# Geral.net
KiCad netlist of a schematic drawn in Altium Designer
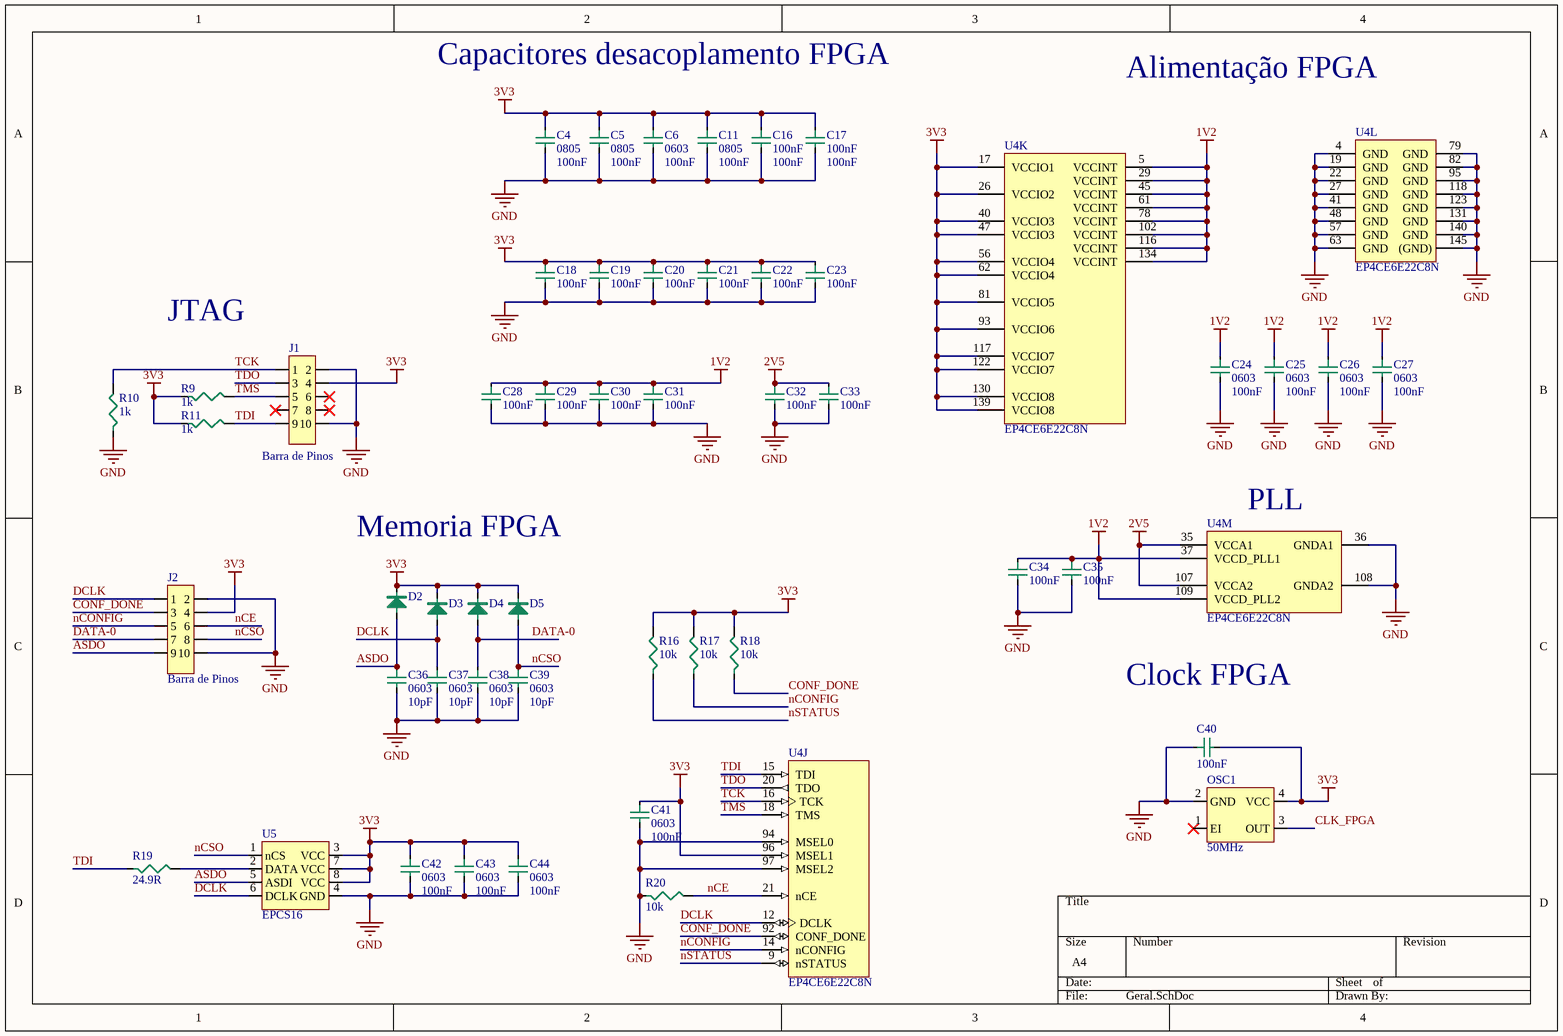
[diagram p0: Geral.SchDoc]

(export (version "E")
  (design (tool "Eeschema 10.0.6"))
  (components
    (comp (ref "C4")
      (value "0805")
      (footprint "0603C")
      (description "Capacitor SMD 0603")
      (fields (field (name "ALTIUM_VALUE") "100nF"))
      (libsource (lib "") (part "Capacitor SMD 0603_1"))
    )
    (comp (ref "C5")
      (value "0805")
      (footprint "0603C")
      (description "Capacitor SMD 0603")
      (fields (field (name "ALTIUM_VALUE") "100nF"))
      (libsource (lib "") (part "Capacitor SMD 0603_1"))
    )
    (comp (ref "C6")
      (value "0603")
      (footprint "0603C")
      (description "Capacitor SMD 0603")
      (fields (field (name "ALTIUM_VALUE") "100nF"))
      (libsource (lib "") (part "Capacitor SMD 0603_1"))
    )
    (comp (ref "C11")
      (value "0805")
      (footprint "0603C")
      (description "Capacitor SMD 0603")
      (fields (field (name "ALTIUM_VALUE") "100nF"))
      (libsource (lib "") (part "Capacitor SMD 0603_1"))
    )
    (comp (ref "C16")
      (value "100nF")
      (footprint "0603C")
      (description "Capacitor SMD 0603")
      (fields (field (name "ALTIUM_VALUE") "100nF"))
      (libsource (lib "RLC_Integrated_Library") (part "Capacitor SMD 0603"))
    )
    (comp (ref "C17")
      (value "100nF")
      (footprint "0603C")
      (description "Capacitor SMD 0603")
      (fields (field (name "ALTIUM_VALUE") "100nF"))
      (libsource (lib "RLC_Integrated_Library") (part "Capacitor SMD 0603"))
    )
    (comp (ref "C18")
      (value "100nF")
      (footprint "0603C")
      (description "Capacitor SMD 0603")
      (libsource (lib "RLC_Integrated_Library") (part "Capacitor SMD 0603"))
    )
    (comp (ref "C19")
      (value "100nF")
      (footprint "0603C")
      (description "Capacitor SMD 0603")
      (libsource (lib "RLC_Integrated_Library") (part "Capacitor SMD 0603"))
    )
    (comp (ref "C20")
      (value "100nF")
      (footprint "0603C")
      (description "Capacitor SMD 0603")
      (libsource (lib "RLC_Integrated_Library") (part "Capacitor SMD 0603"))
    )
    (comp (ref "C21")
      (value "100nF")
      (footprint "0603C")
      (description "Capacitor SMD 0603")
      (libsource (lib "RLC_Integrated_Library") (part "Capacitor SMD 0603"))
    )
    (comp (ref "C22")
      (value "100nF")
      (footprint "0603C")
      (description "Capacitor SMD 0603")
      (libsource (lib "RLC_Integrated_Library") (part "Capacitor SMD 0603"))
    )
    (comp (ref "C23")
      (value "100nF")
      (footprint "0603C")
      (description "Capacitor SMD 0603")
      (libsource (lib "RLC_Integrated_Library") (part "Capacitor SMD 0603"))
    )
    (comp (ref "C24")
      (value "0603")
      (footprint "0603C")
      (description "Capacitor SMD 0603")
      (fields (field (name "ALTIUM_VALUE") "100nF"))
      (libsource (lib "") (part "Capacitor SMD 0603_1"))
    )
    (comp (ref "C25")
      (value "0603")
      (footprint "0603C")
      (description "Capacitor SMD 0603")
      (fields (field (name "ALTIUM_VALUE") "100nF"))
      (libsource (lib "") (part "Capacitor SMD 0603_1"))
    )
    (comp (ref "C26")
      (value "0603")
      (footprint "0603C")
      (description "Capacitor SMD 0603")
      (fields (field (name "ALTIUM_VALUE") "100nF"))
      (libsource (lib "") (part "Capacitor SMD 0603_1"))
    )
    (comp (ref "C27")
      (value "0603")
      (footprint "0603C")
      (description "Capacitor SMD 0603")
      (fields (field (name "ALTIUM_VALUE") "100nF"))
      (libsource (lib "") (part "Capacitor SMD 0603_1"))
    )
    (comp (ref "C28")
      (value "100nF")
      (footprint "0603C")
      (description "Capacitor SMD 0603")
      (libsource (lib "RLC_Integrated_Library") (part "Capacitor SMD 0603"))
    )
    (comp (ref "C29")
      (value "100nF")
      (footprint "0603C")
      (description "Capacitor SMD 0603")
      (libsource (lib "RLC_Integrated_Library") (part "Capacitor SMD 0603"))
    )
    (comp (ref "C30")
      (value "100nF")
      (footprint "0603C")
      (description "Capacitor SMD 0603")
      (libsource (lib "RLC_Integrated_Library") (part "Capacitor SMD 0603"))
    )
    (comp (ref "C31")
      (value "100nF")
      (footprint "0603C")
      (description "Capacitor SMD 0603")
      (libsource (lib "RLC_Integrated_Library") (part "Capacitor SMD 0603"))
    )
    (comp (ref "C32")
      (value "100nF")
      (footprint "0603C")
      (description "Capacitor SMD 0603")
      (libsource (lib "RLC_Integrated_Library") (part "Capacitor SMD 0603"))
    )
    (comp (ref "C33")
      (value "100nF")
      (footprint "0603C")
      (description "Capacitor SMD 0603")
      (libsource (lib "RLC_Integrated_Library") (part "Capacitor SMD 0603"))
    )
    (comp (ref "C34")
      (value "100nF")
      (footprint "0603C")
      (description "Capacitor SMD 0603")
      (libsource (lib "RLC_Integrated_Library") (part "Capacitor SMD 0603"))
    )
    (comp (ref "C35")
      (value "100nF")
      (footprint "0603C")
      (description "Capacitor SMD 0603")
      (libsource (lib "RLC_Integrated_Library") (part "Capacitor SMD 0603"))
    )
    (comp (ref "C36")
      (value "0603")
      (footprint "0603C")
      (description "Capacitor SMD 0603")
      (fields (field (name "ALTIUM_VALUE") "10pF"))
      (libsource (lib "") (part "Capacitor SMD 0603_1"))
    )
    (comp (ref "C37")
      (value "0603")
      (footprint "0603C")
      (description "Capacitor SMD 0603")
      (fields (field (name "ALTIUM_VALUE") "10pF"))
      (libsource (lib "") (part "Capacitor SMD 0603_1"))
    )
    (comp (ref "C38")
      (value "0603")
      (footprint "0603C")
      (description "Capacitor SMD 0603")
      (fields (field (name "ALTIUM_VALUE") "10pF"))
      (libsource (lib "") (part "Capacitor SMD 0603_1"))
    )
    (comp (ref "C39")
      (value "0603")
      (footprint "0603C")
      (description "Capacitor SMD 0603")
      (fields (field (name "ALTIUM_VALUE") "10pF"))
      (libsource (lib "") (part "Capacitor SMD 0603_1"))
    )
    (comp (ref "C40")
      (value "100nF")
      (footprint "0603C")
      (description "Capacitor SMD 0603")
      (fields (field (name "Comment") "10pF"))
      (libsource (lib "") (part "Capacitor SMD 0603_1"))
    )
    (comp (ref "C41")
      (value "0603")
      (footprint "0603C")
      (description "Capacitor SMD 0603")
      (fields (field (name "ALTIUM_VALUE") "100nF"))
      (libsource (lib "") (part "Capacitor SMD 0603_1"))
    )
    (comp (ref "C42")
      (value "0603")
      (footprint "0603C")
      (description "Capacitor SMD 0603")
      (fields (field (name "ALTIUM_VALUE") "100nF"))
      (libsource (lib "") (part "Capacitor SMD 0603_1"))
    )
    (comp (ref "C43")
      (value "0603")
      (footprint "0603C")
      (description "Capacitor SMD 0603")
      (fields (field (name "ALTIUM_VALUE") "100nF"))
      (libsource (lib "") (part "Capacitor SMD 0603_1"))
    )
    (comp (ref "C44")
      (value "0603")
      (footprint "0603C")
      (description "Capacitor SMD 0603")
      (fields (field (name "ALTIUM_VALUE") "100nF"))
      (libsource (lib "") (part "Capacitor SMD 0603_1"))
    )
    (comp (ref "D2")
      (value "1N4148 SMD")
      (footprint "DIODE SMD LL-34")
      (description "Diodo Sinal SMD LL-34")
      (libsource (lib "Diodo_Transistor_Integrated_Library") (part "Diodo Sinal SMD 1N4148"))
    )
    (comp (ref "D3")
      (value "1N4148 SMD")
      (footprint "DIODE SMD LL-34")
      (description "Diodo Sinal SMD LL-34")
      (libsource (lib "Diodo_Transistor_Integrated_Library") (part "Diodo Sinal SMD 1N4148"))
    )
    (comp (ref "D4")
      (value "1N4148 SMD")
      (footprint "DIODE SMD LL-34")
      (description "Diodo Sinal SMD LL-34")
      (libsource (lib "Diodo_Transistor_Integrated_Library") (part "Diodo Sinal SMD 1N4148"))
    )
    (comp (ref "D5")
      (value "1N4148 SMD")
      (footprint "DIODE SMD LL-34")
      (description "Diodo Sinal SMD LL-34")
      (libsource (lib "Diodo_Transistor_Integrated_Library") (part "Diodo Sinal SMD 1N4148"))
    )
    (comp (ref "J1")
      (value "Barra de Pinos")
      (footprint "BPDC-10")
      (description "Barra 5X2 Pinos PTH")
      (fields (field (name "MANUFACTURER") "Metaltex"))
      (libsource (lib "Schlib1") (part "Barra 5X2 Pinos PTH"))
    )
    (comp (ref "J2")
      (value "Barra de Pinos")
      (footprint "BPDC-10")
      (description "Barra 5X2 Pinos PTH")
      (fields (field (name "MANUFACTURER") "Metaltex"))
      (libsource (lib "Schlib1") (part "Barra 5X2 Pinos PTH"))
    )
    (comp (ref "OSC1")
      (value "50MHz")
      (footprint "OSC CB3LV")
      (description "OSC XO 50.00MHZ HCMOS TTL SMD")
      (libsource (lib "Schlib1") (part "OSCILLATOR_INEP"))
    )
    (comp (ref "R9")
      (value "1k")
      (footprint "0603")
      (description "Resistor SMD 0603 1/10 W")
      (fields (field (name "Comment") "0603"))
      (libsource (lib "RLC_Integrated_Library") (part "Resistor SMD 0603 1/10 W"))
    )
    (comp (ref "R10")
      (value "1k")
      (footprint "0603")
      (description "Resistor SMD 0603 1/10 W")
      (fields (field (name "Comment") "0603"))
      (libsource (lib "RLC_Integrated_Library") (part "Resistor SMD 0603 1/10 W"))
    )
    (comp (ref "R11")
      (value "1k")
      (footprint "0603")
      (description "Resistor SMD 0603 1/10 W")
      (fields (field (name "Comment") "0603"))
      (libsource (lib "RLC_Integrated_Library") (part "Resistor SMD 0603 1/10 W"))
    )
    (comp (ref "R16")
      (value "10k")
      (footprint "0603")
      (description "Resistor SMD 0603 1/10 W")
      (fields (field (name "Comment") "100R"))
      (libsource (lib "RLC_Integrated_Library") (part "Resistor SMD 0603 1/10 W"))
    )
    (comp (ref "R17")
      (value "10k")
      (footprint "0603")
      (description "Resistor SMD 0603 1/10 W")
      (fields (field (name "Comment") "1K"))
      (libsource (lib "RLC_Integrated_Library") (part "Resistor SMD 0603 1/10 W"))
    )
    (comp (ref "R18")
      (value "10k")
      (footprint "0603")
      (description "Resistor SMD 0603 1/10 W")
      (fields (field (name "Comment") "1K"))
      (libsource (lib "RLC_Integrated_Library") (part "Resistor SMD 0603 1/10 W"))
    )
    (comp (ref "R19")
      (value "24.9R")
      (footprint "0603")
      (description "Resistor SMD 0603 1/10 W")
      (fields (field (name "Comment") "1K"))
      (libsource (lib "RLC_Integrated_Library") (part "Resistor SMD 0603 1/10 W"))
    )
    (comp (ref "R20")
      (value "10k")
      (footprint "0603")
      (description "Resistor SMD 0603 1/10 W")
      (fields (field (name "Comment") "10K"))
      (libsource (lib "RLC_Integrated_Library") (part "Resistor SMD 0603 1/10 W"))
    )
    (comp (ref "U4")
      (value "EP4CE6E22C8N")
      (footprint "EQFP144_M")
      (description "IC FPGA 91 I/O 144EQFP")
      (libsource (lib "Schlib1") (part "EP4CE6E22C8N"))
    )
    (comp (ref "U5")
      (value "EPCS16")
      (footprint "SOIC8")
      (description "IC CONFIG DEVICE 16MBIT 8SOIC")
      (libsource (lib "Schlib1") (part "EPCS16SI8N"))
    )
  )
  (nets
    (net (code "1") (name "/ASDO") (class "Default")
      (node (ref "C36") (pin "1") (pinfunction "1_1") (pintype "passive"))
      (node (ref "D2") (pin "A") (pinfunction "A_A") (pintype "passive"))
      (node (ref "J2") (pin "9") (pinfunction "9_9") (pintype "passive"))
      (node (ref "U5") (pin "5") (pinfunction "ASDI_5") (pintype "passive"))
    )
    (net (code "2") (name "/CLK_FPGA") (class "Default")
      (node (ref "OSC1") (pin "3") (pinfunction "OUT_3") (pintype "passive"))
    )
    (net (code "3") (name "/CONF_DONE") (class "Default")
      (node (ref "J2") (pin "3") (pinfunction "3_3") (pintype "passive"))
      (node (ref "R18") (pin "1") (pinfunction "1_1") (pintype "passive"))
      (node (ref "U4") (pin "92") (pinfunction "CONF_DONE_92") (pintype "bidirectional"))
    )
    (net (code "4") (name "/DATA-0") (class "Default")
      (node (ref "C38") (pin "1") (pinfunction "1_1") (pintype "passive"))
      (node (ref "D4") (pin "A") (pinfunction "A_A") (pintype "passive"))
      (node (ref "J2") (pin "7") (pinfunction "7_7") (pintype "passive"))
    )
    (net (code "5") (name "/DCLK") (class "Default")
      (node (ref "C37") (pin "1") (pinfunction "1_1") (pintype "passive"))
      (node (ref "D3") (pin "A") (pinfunction "A_A") (pintype "passive"))
      (node (ref "J2") (pin "1") (pinfunction "1_1") (pintype "passive"))
      (node (ref "U4") (pin "12") (pinfunction "DCLK_12") (pintype "bidirectional"))
      (node (ref "U5") (pin "6") (pinfunction "DCLK_6") (pintype "passive"))
    )
    (net (code "6") (name "/TCK") (class "Default")
      (node (ref "J1") (pin "1") (pinfunction "1_1") (pintype "passive"))
      (node (ref "R10") (pin "2") (pinfunction "2_2") (pintype "passive"))
      (node (ref "U4") (pin "16") (pinfunction "TCK_16") (pintype "input"))
    )
    (net (code "7") (name "/TDI") (class "Default")
      (node (ref "J1") (pin "9") (pinfunction "9_9") (pintype "passive"))
      (node (ref "R11") (pin "2") (pinfunction "2_2") (pintype "passive"))
      (node (ref "R19") (pin "1") (pinfunction "1_1") (pintype "passive"))
      (node (ref "U4") (pin "15") (pinfunction "TDI_15") (pintype "input"))
    )
    (net (code "8") (name "/TDO") (class "Default")
      (node (ref "J1") (pin "3") (pinfunction "3_3") (pintype "passive"))
      (node (ref "U4") (pin "20") (pinfunction "TDO_20") (pintype "output"))
    )
    (net (code "9") (name "/TMS") (class "Default")
      (node (ref "J1") (pin "5") (pinfunction "5_5") (pintype "passive"))
      (node (ref "R9") (pin "2") (pinfunction "2_2") (pintype "passive"))
      (node (ref "U4") (pin "18") (pinfunction "TMS_18") (pintype "input"))
    )
    (net (code "10") (name "/nCE") (class "Default")
      (node (ref "J2") (pin "6") (pinfunction "6_6") (pintype "passive"))
      (node (ref "R20") (pin "2") (pinfunction "2_2") (pintype "passive"))
      (node (ref "U4") (pin "21") (pinfunction "nCE_21") (pintype "input"))
    )
    (net (code "11") (name "/nCONFIG") (class "Default")
      (node (ref "J2") (pin "5") (pinfunction "5_5") (pintype "passive"))
      (node (ref "R17") (pin "1") (pinfunction "1_1") (pintype "passive"))
      (node (ref "U4") (pin "14") (pinfunction "nCONFIG_14") (pintype "input"))
    )
    (net (code "12") (name "/nCSO") (class "Default")
      (node (ref "C39") (pin "1") (pinfunction "1_1") (pintype "passive"))
      (node (ref "D5") (pin "A") (pinfunction "A_A") (pintype "passive"))
      (node (ref "J2") (pin "8") (pinfunction "8_8") (pintype "passive"))
      (node (ref "U5") (pin "1") (pinfunction "nCS_1") (pintype "passive"))
    )
    (net (code "13") (name "/nSTATUS") (class "Default")
      (node (ref "R16") (pin "1") (pinfunction "1_1") (pintype "passive"))
      (node (ref "U4") (pin "9") (pinfunction "nSTATUS_9") (pintype "bidirectional"))
    )
    (net (code "14") (name "1V2") (class "Default")
      (node (ref "C24") (pin "1") (pinfunction "1_1") (pintype "passive"))
      (node (ref "C25") (pin "1") (pinfunction "1_1") (pintype "passive"))
      (node (ref "C26") (pin "1") (pinfunction "1_1") (pintype "passive"))
      (node (ref "C27") (pin "1") (pinfunction "1_1") (pintype "passive"))
      (node (ref "C28") (pin "2") (pinfunction "2_2") (pintype "passive"))
      (node (ref "C29") (pin "2") (pinfunction "2_2") (pintype "passive"))
      (node (ref "C30") (pin "2") (pinfunction "2_2") (pintype "passive"))
      (node (ref "C31") (pin "2") (pinfunction "2_2") (pintype "passive"))
      (node (ref "C34") (pin "2") (pinfunction "2_2") (pintype "passive"))
      (node (ref "C35") (pin "2") (pinfunction "2_2") (pintype "passive"))
      (node (ref "U4") (pin "102") (pinfunction "VCCINT_102") (pintype "power_in"))
      (node (ref "U4") (pin "109") (pinfunction "VCCD_PLL2_109") (pintype "power_in"))
      (node (ref "U4") (pin "116") (pinfunction "VCCINT_116") (pintype "power_in"))
      (node (ref "U4") (pin "134") (pinfunction "VCCINT_134") (pintype "power_in"))
      (node (ref "U4") (pin "29") (pinfunction "VCCINT_29") (pintype "power_in"))
      (node (ref "U4") (pin "37") (pinfunction "VCCD_PLL1_37") (pintype "power_in"))
      (node (ref "U4") (pin "45") (pinfunction "VCCINT_45") (pintype "power_in"))
      (node (ref "U4") (pin "5") (pinfunction "VCCINT_5") (pintype "power_in"))
      (node (ref "U4") (pin "61") (pinfunction "VCCINT_61") (pintype "power_in"))
      (node (ref "U4") (pin "78") (pinfunction "VCCINT_78") (pintype "power_in"))
    )
    (net (code "15") (name "2V5") (class "Default")
      (node (ref "C32") (pin "2") (pinfunction "2_2") (pintype "passive"))
      (node (ref "C33") (pin "2") (pinfunction "2_2") (pintype "passive"))
      (node (ref "U4") (pin "107") (pinfunction "VCCA2_107") (pintype "power_in"))
      (node (ref "U4") (pin "35") (pinfunction "VCCA1_35") (pintype "power_in"))
    )
    (net (code "16") (name "3V3") (class "Default")
      (node (ref "C11") (pin "1") (pinfunction "1_1") (pintype "passive"))
      (node (ref "C16") (pin "2") (pinfunction "2_2") (pintype "passive"))
      (node (ref "C17") (pin "2") (pinfunction "2_2") (pintype "passive"))
      (node (ref "C18") (pin "2") (pinfunction "2_2") (pintype "passive"))
      (node (ref "C19") (pin "2") (pinfunction "2_2") (pintype "passive"))
      (node (ref "C20") (pin "2") (pinfunction "2_2") (pintype "passive"))
      (node (ref "C21") (pin "2") (pinfunction "2_2") (pintype "passive"))
      (node (ref "C22") (pin "2") (pinfunction "2_2") (pintype "passive"))
      (node (ref "C23") (pin "2") (pinfunction "2_2") (pintype "passive"))
      (node (ref "C4") (pin "1") (pinfunction "1_1") (pintype "passive"))
      (node (ref "C40") (pin "2") (pinfunction "2_2") (pintype "passive"))
      (node (ref "C41") (pin "1") (pinfunction "1_1") (pintype "passive"))
      (node (ref "C42") (pin "1") (pinfunction "1_1") (pintype "passive"))
      (node (ref "C43") (pin "1") (pinfunction "1_1") (pintype "passive"))
      (node (ref "C44") (pin "1") (pinfunction "1_1") (pintype "passive"))
      (node (ref "C5") (pin "1") (pinfunction "1_1") (pintype "passive"))
      (node (ref "C6") (pin "1") (pinfunction "1_1") (pintype "passive"))
      (node (ref "D2") (pin "K") (pinfunction "K_K") (pintype "passive"))
      (node (ref "D3") (pin "K") (pinfunction "K_K") (pintype "passive"))
      (node (ref "D4") (pin "K") (pinfunction "K_K") (pintype "passive"))
      (node (ref "D5") (pin "K") (pinfunction "K_K") (pintype "passive"))
      (node (ref "J1") (pin "4") (pinfunction "4_4") (pintype "passive"))
      (node (ref "J2") (pin "4") (pinfunction "4_4") (pintype "passive"))
      (node (ref "OSC1") (pin "4") (pinfunction "VCC_4") (pintype "passive"))
      (node (ref "R11") (pin "1") (pinfunction "1_1") (pintype "passive"))
      (node (ref "R16") (pin "2") (pinfunction "2_2") (pintype "passive"))
      (node (ref "R17") (pin "2") (pinfunction "2_2") (pintype "passive"))
      (node (ref "R18") (pin "2") (pinfunction "2_2") (pintype "passive"))
      (node (ref "R9") (pin "1") (pinfunction "1_1") (pintype "passive"))
      (node (ref "U4") (pin "117") (pinfunction "VCCIO7_117") (pintype "power_in"))
      (node (ref "U4") (pin "122") (pinfunction "VCCIO7_122") (pintype "power_in"))
      (node (ref "U4") (pin "130") (pinfunction "VCCIO8_130") (pintype "power_in"))
      (node (ref "U4") (pin "139") (pinfunction "VCCIO8_139") (pintype "power_in"))
      (node (ref "U4") (pin "17") (pinfunction "VCCIO1_17") (pintype "power_in"))
      (node (ref "U4") (pin "26") (pinfunction "VCCIO2_26") (pintype "power_in"))
      (node (ref "U4") (pin "40") (pinfunction "VCCIO3_40") (pintype "power_in"))
      (node (ref "U4") (pin "47") (pinfunction "VCCIO3_47") (pintype "power_in"))
      (node (ref "U4") (pin "56") (pinfunction "VCCIO4_56") (pintype "power_in"))
      (node (ref "U4") (pin "62") (pinfunction "VCCIO4_62") (pintype "power_in"))
      (node (ref "U4") (pin "81") (pinfunction "VCCIO5_81") (pintype "power_in"))
      (node (ref "U4") (pin "93") (pinfunction "VCCIO6_93") (pintype "power_in"))
      (node (ref "U4") (pin "96") (pinfunction "MSEL1_96") (pintype "input"))
      (node (ref "U5") (pin "3") (pinfunction "VCC_3") (pintype "passive"))
      (node (ref "U5") (pin "7") (pinfunction "VCC_7") (pintype "passive"))
      (node (ref "U5") (pin "8") (pinfunction "VCC_8") (pintype "passive"))
    )
    (net (code "17") (name "GND") (class "Default")
      (node (ref "C11") (pin "2") (pinfunction "2_2") (pintype "passive"))
      (node (ref "C16") (pin "1") (pinfunction "1_1") (pintype "passive"))
      (node (ref "C17") (pin "1") (pinfunction "1_1") (pintype "passive"))
      (node (ref "C18") (pin "1") (pinfunction "1_1") (pintype "passive"))
      (node (ref "C19") (pin "1") (pinfunction "1_1") (pintype "passive"))
      (node (ref "C20") (pin "1") (pinfunction "1_1") (pintype "passive"))
      (node (ref "C21") (pin "1") (pinfunction "1_1") (pintype "passive"))
      (node (ref "C22") (pin "1") (pinfunction "1_1") (pintype "passive"))
      (node (ref "C23") (pin "1") (pinfunction "1_1") (pintype "passive"))
      (node (ref "C24") (pin "2") (pinfunction "2_2") (pintype "passive"))
      (node (ref "C25") (pin "2") (pinfunction "2_2") (pintype "passive"))
      (node (ref "C26") (pin "2") (pinfunction "2_2") (pintype "passive"))
      (node (ref "C27") (pin "2") (pinfunction "2_2") (pintype "passive"))
      (node (ref "C28") (pin "1") (pinfunction "1_1") (pintype "passive"))
      (node (ref "C29") (pin "1") (pinfunction "1_1") (pintype "passive"))
      (node (ref "C30") (pin "1") (pinfunction "1_1") (pintype "passive"))
      (node (ref "C31") (pin "1") (pinfunction "1_1") (pintype "passive"))
      (node (ref "C32") (pin "1") (pinfunction "1_1") (pintype "passive"))
      (node (ref "C33") (pin "1") (pinfunction "1_1") (pintype "passive"))
      (node (ref "C34") (pin "1") (pinfunction "1_1") (pintype "passive"))
      (node (ref "C35") (pin "1") (pinfunction "1_1") (pintype "passive"))
      (node (ref "C36") (pin "2") (pinfunction "2_2") (pintype "passive"))
      (node (ref "C37") (pin "2") (pinfunction "2_2") (pintype "passive"))
      (node (ref "C38") (pin "2") (pinfunction "2_2") (pintype "passive"))
      (node (ref "C39") (pin "2") (pinfunction "2_2") (pintype "passive"))
      (node (ref "C4") (pin "2") (pinfunction "2_2") (pintype "passive"))
      (node (ref "C40") (pin "1") (pinfunction "1_1") (pintype "passive"))
      (node (ref "C41") (pin "2") (pinfunction "2_2") (pintype "passive"))
      (node (ref "C42") (pin "2") (pinfunction "2_2") (pintype "passive"))
      (node (ref "C43") (pin "2") (pinfunction "2_2") (pintype "passive"))
      (node (ref "C44") (pin "2") (pinfunction "2_2") (pintype "passive"))
      (node (ref "C5") (pin "2") (pinfunction "2_2") (pintype "passive"))
      (node (ref "C6") (pin "2") (pinfunction "2_2") (pintype "passive"))
      (node (ref "J1") (pin "10") (pinfunction "10_10") (pintype "passive"))
      (node (ref "J1") (pin "2") (pinfunction "2_2") (pintype "passive"))
      (node (ref "J2") (pin "10") (pinfunction "10_10") (pintype "passive"))
      (node (ref "J2") (pin "2") (pinfunction "2_2") (pintype "passive"))
      (node (ref "OSC1") (pin "2") (pinfunction "GND_2") (pintype "passive"))
      (node (ref "R10") (pin "1") (pinfunction "1_1") (pintype "passive"))
      (node (ref "R20") (pin "1") (pinfunction "1_1") (pintype "passive"))
      (node (ref "U4") (pin "108") (pinfunction "GNDA2_108") (pintype "power_in"))
      (node (ref "U4") (pin "118") (pinfunction "GND_118") (pintype "power_in"))
      (node (ref "U4") (pin "123") (pinfunction "GND_123") (pintype "power_in"))
      (node (ref "U4") (pin "131") (pinfunction "GND_131") (pintype "power_in"))
      (node (ref "U4") (pin "140") (pinfunction "GND_140") (pintype "power_in"))
      (node (ref "U4") (pin "145") (pinfunction "(GND)_145") (pintype "power_in"))
      (node (ref "U4") (pin "19") (pinfunction "GND_19") (pintype "power_in"))
      (node (ref "U4") (pin "22") (pinfunction "GND_22") (pintype "power_in"))
      (node (ref "U4") (pin "27") (pinfunction "GND_27") (pintype "power_in"))
      (node (ref "U4") (pin "36") (pinfunction "GNDA1_36") (pintype "power_in"))
      (node (ref "U4") (pin "4") (pinfunction "GND_4") (pintype "power_in"))
      (node (ref "U4") (pin "41") (pinfunction "GND_41") (pintype "power_in"))
      (node (ref "U4") (pin "48") (pinfunction "GND_48") (pintype "power_in"))
      (node (ref "U4") (pin "57") (pinfunction "GND_57") (pintype "power_in"))
      (node (ref "U4") (pin "63") (pinfunction "GND_63") (pintype "power_in"))
      (node (ref "U4") (pin "79") (pinfunction "GND_79") (pintype "power_in"))
      (node (ref "U4") (pin "82") (pinfunction "GND_82") (pintype "power_in"))
      (node (ref "U4") (pin "94") (pinfunction "MSEL0_94") (pintype "input"))
      (node (ref "U4") (pin "95") (pinfunction "GND_95") (pintype "power_in"))
      (node (ref "U4") (pin "97") (pinfunction "MSEL2_97") (pintype "input"))
      (node (ref "U5") (pin "4") (pinfunction "GND_4") (pintype "passive"))
    )
    (net (code "18") (name "Net-(U5-DATA)") (class "Default")
      (node (ref "R19") (pin "2") (pinfunction "2_2") (pintype "passive"))
      (node (ref "U5") (pin "2") (pinfunction "DATA_2") (pintype "passive"))
    )
    (net (code "19") (name "unconnected-(J1-Pad6)") (class "Default")
      (node (ref "J1") (pin "6") (pinfunction "6_6") (pintype "passive+no_connect"))
    )
    (net (code "20") (name "unconnected-(J1-Pad7)") (class "Default")
      (node (ref "J1") (pin "7") (pinfunction "7_7") (pintype "passive+no_connect"))
    )
    (net (code "21") (name "unconnected-(J1-Pad8)") (class "Default")
      (node (ref "J1") (pin "8") (pinfunction "8_8") (pintype "passive+no_connect"))
    )
    (net (code "22") (name "unconnected-(OSC1-EI-Pad1)") (class "Default")
      (node (ref "OSC1") (pin "1") (pinfunction "EI_1") (pintype "passive+no_connect"))
    )
  )
)
